# Audio_Module.net
KiCad netlist of a schematic drawn in Altium Designer
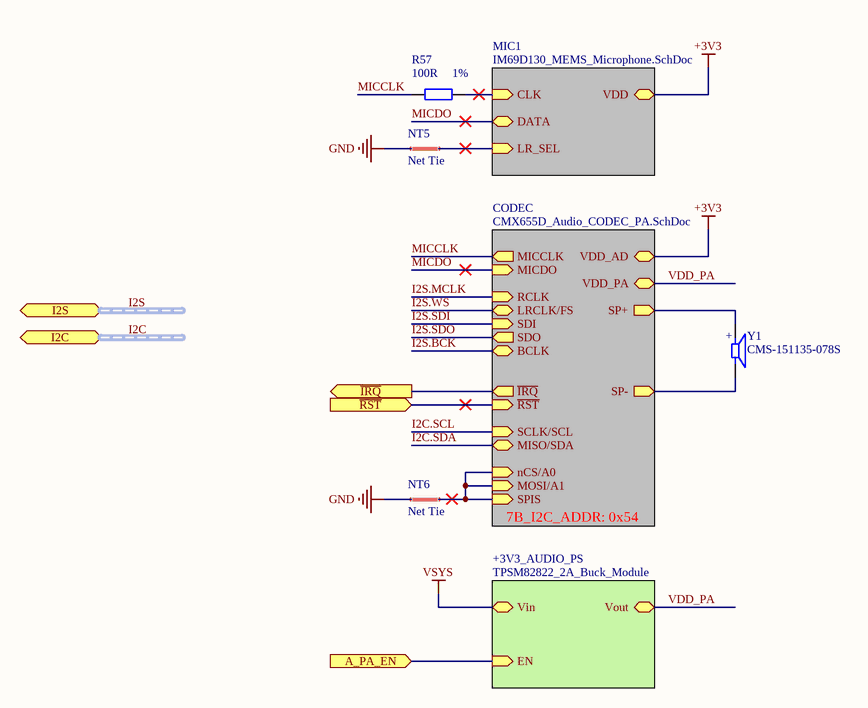
[diagram p0: Audio_Module.SchDoc]

(export (version "E")
  (design (tool "Eeschema 10.0.6"))
  (components
    (comp (ref "NT5")
      (value "Net Tie")
      (footprint "Net Tie 6x30mil")
      (libsource (lib "BLDC_Motor_Driver") (part "Net Tie Line"))
    )
    (comp (ref "NT6")
      (value "Net Tie")
      (footprint "Net Tie 6x30mil")
      (libsource (lib "BLDC_Motor_Driver") (part "Net Tie Line"))
    )
    (comp (ref "R57")
      (value "RES SMD 100 OHM 1% 1/16W 0402")
      (footprint "0402R")
      (description "100 Ohms ±1% 0.063W, 1/16W Chip Resistor 0402 (1005 Metric) Moisture Resistant Thick Film")
      (fields
        (field (name "MANUFACTURER") "Yageo")
        (field (name "MANUFACTURER PART NUMBER") "RC0402FR-07100RL")
        (field (name "TOLERANCE") "1%")
        (field (name "RESISTANCE") "100R")
      )
      (libsource (lib "resistors_smd") (part "RES SMD 100 OHM 1% 1/16W 0402"))
    )
    (comp (ref "Y1")
      (value "CMS-151135-078S")
      (footprint "SPKR_CMS-151135-078S")
      (description "8 Ohms General Purpose Speaker 700mW 100Hz ~ 20kHz Top Rectangular")
      (fields (field (name "MANUFACTURER") "CUI"))
      (libsource (lib "BLDC_Motor_Driver") (part "SPEAKER CMS-151135-078S 15 X 11 MM ENCLOSED"))
    )
  )
  (nets
    (net (code "5") (name "/CLK") (class "Default")
      (node (ref "R57") (pin "1") (pinfunction "1_1") (pintype "passive"))
    )
    (net (code "14") (name "/LR_SEL") (class "Default") (node (ref "NT5") (pin "2") (pintype "passive")))
    (net (code "15") (name "/MICCLK") (class "Default")
      (node (ref "R57") (pin "2") (pinfunction "2_2") (pintype "passive"))
    )
    (net (code "17") (name "/MOSI{slash}A1") (class "Default")
      (node (ref "NT6") (pin "2") (pintype "passive"))
    )
    (net (code "19") (name "/SP+") (class "Default")
      (node (ref "Y1") (pin "P") (pinfunction "1_P") (pintype "passive"))
    )
    (net (code "20") (name "/SP-") (class "Default")
      (node (ref "Y1") (pin "M") (pinfunction "2_M") (pintype "passive"))
    )
    (net (code "24") (name "GND") (class "Default")
      (node (ref "NT5") (pin "1") (pintype "passive"))
      (node (ref "NT6") (pin "1") (pintype "passive"))
    )
  )
)
